# avr_programming_shield_built.net
KiCad netlist of a schematic drawn in EAGLE
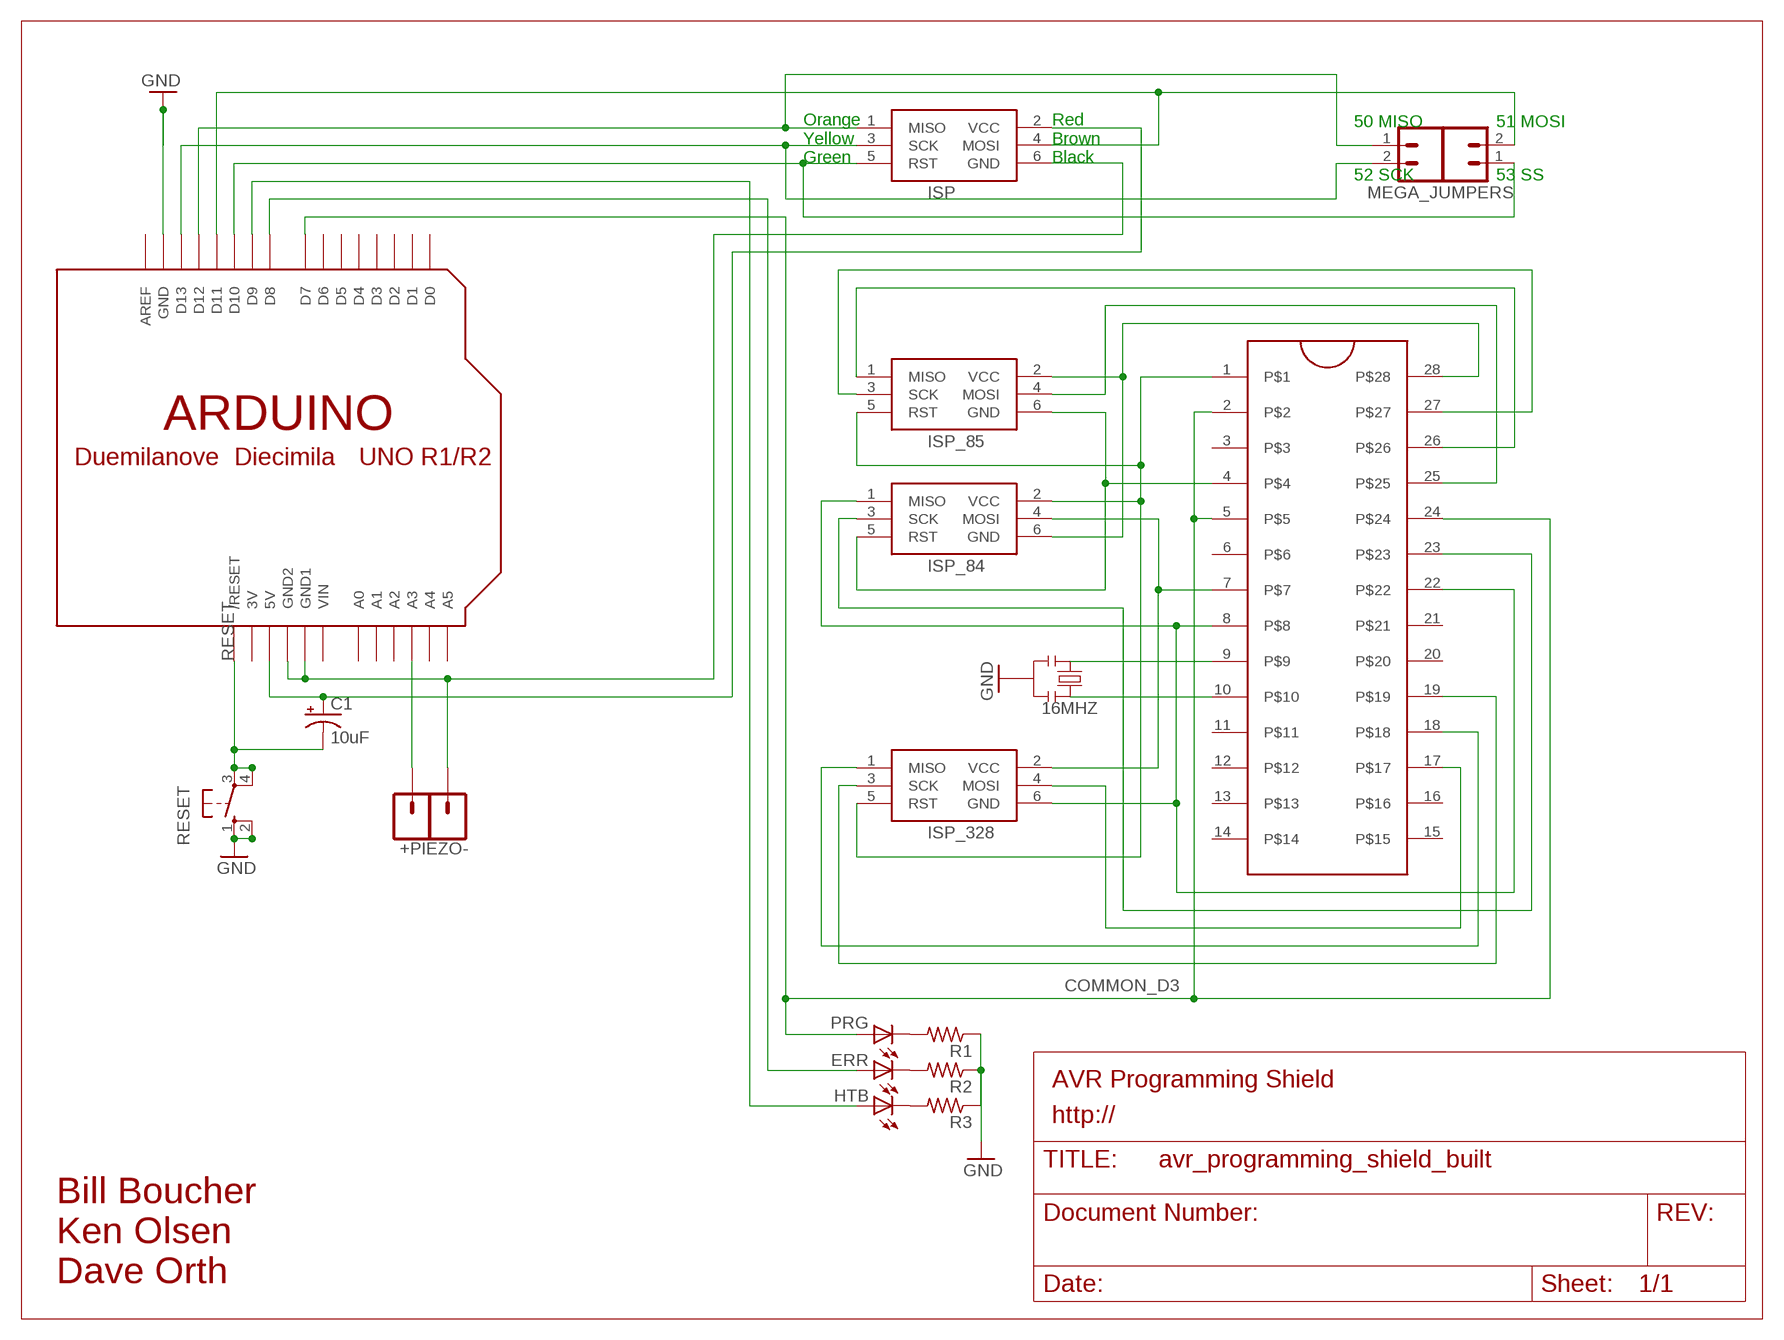
[diagram p0: schematic, sheet 1]

(export (version "E")
  (design (tool "Eeschema 10.0.6"))
  (components
    (comp (ref "+PIEZO-")
      (value "M01PTH")
      (footprint "eagle-import:1X01")
      (libsource (lib "eagle-import") (part "M01PTH"))
    )
    (comp (ref "16MHZ")
      (value "RESONATORPTH")
      (footprint "eagle-import:RESONATOR-PTH")
      (libsource (lib "eagle-import") (part "RESONATORPTH"))
    )
    (comp (ref "C1")
      (value "10uF")
      (footprint "eagle-import:CPOL-RADIAL-10UF-25V")
      (fields (field (name "MF") "ILLINOIS CAPACITOR,INC.") (field (name "MPN") "106TTA035M"))
      (libsource (lib "eagle-import") (part "CAP_POLPTH2"))
    )
    (comp (ref "ERR")
      (value "LED3MM")
      (footprint "eagle-import:LED3MM")
      (libsource (lib "eagle-import") (part "LED3MM"))
    )
    (comp (ref "HTB")
      (value "LED3MM")
      (footprint "eagle-import:LED3MM")
      (libsource (lib "eagle-import") (part "LED3MM"))
    )
    (comp (ref "ISP")
      (value "AVRISP-6")
      (footprint "eagle-import:AVRISP")
      (libsource (lib "eagle-import") (part "AVRISP-6"))
    )
    (comp (ref "ISP_84")
      (value "AVRISP-6")
      (footprint "eagle-import:AVRISP")
      (libsource (lib "eagle-import") (part "AVRISP-6"))
    )
    (comp (ref "ISP_85")
      (value "AVRISP-6")
      (footprint "eagle-import:AVRISP")
      (libsource (lib "eagle-import") (part "AVRISP-6"))
    )
    (comp (ref "ISP_328")
      (value "AVRISP-6")
      (footprint "eagle-import:AVRISP")
      (libsource (lib "eagle-import") (part "AVRISP-6"))
    )
    (comp (ref "JP2")
      (value "M02PTH")
      (footprint "eagle-import:1X02")
      (libsource (lib "eagle-import") (part "M02PTH"))
    )
    (comp (ref "JP4")
      (value "M01PTH")
      (footprint "eagle-import:1X01")
      (libsource (lib "eagle-import") (part "M01PTH"))
    )
    (comp (ref "MEGA_JUMPERS")
      (value "M02PTH")
      (footprint "eagle-import:1X02")
      (libsource (lib "eagle-import") (part "M02PTH"))
    )
    (comp (ref "PRG")
      (value "LED3MM")
      (footprint "eagle-import:LED3MM")
      (libsource (lib "eagle-import") (part "LED3MM"))
    )
    (comp (ref "R1")
      (value "R-US_0204/2V")
      (footprint "eagle-import:0204V")
      (libsource (lib "eagle-import") (part "R-US_0204/2V"))
    )
    (comp (ref "R2")
      (value "R-US_0204/2V")
      (footprint "eagle-import:0204V")
      (libsource (lib "eagle-import") (part "R-US_0204/2V"))
    )
    (comp (ref "R3")
      (value "R-US_0204/2V")
      (footprint "eagle-import:0204V")
      (libsource (lib "eagle-import") (part "R-US_0204/2V"))
    )
    (comp (ref "RESET")
      (value "10-XX")
      (footprint "eagle-import:B3F-10XX")
      (fields
        (field (name "MPN") "B3F-1000")
        (field (name "MPN_1") "B3F-1000")
        (field (name "OC_NEWARK") "36M3542")
      )
      (libsource (lib "eagle-import") (part "10-XX"))
    )
    (comp (ref "U$1")
      (value "ARDUINO-NOHOLE")
      (footprint "eagle-import:ARDUINO-NOHOLE")
      (libsource (lib "eagle-import") (part "ARDUINO-NOHOLE"))
    )
    (comp (ref "U$4")
      (value "ZIFSOCKET-28-3ZIFFSOCKET-28-3")
      (footprint "eagle-import:DIL28-3-ZIF_SOCKET")
      (libsource (lib "eagle-import") (part "ZIFSOCKET-28-3ZIFFSOCKET-28-3"))
    )
  )
  (nets
    (net (code "1") (name "/3V") (class "Default")
      (node (ref "U$1") (pin "3V") (pinfunction "3V_3V") (pintype "power_in"))
    )
    (net (code "2") (name "/COMMON_D3") (class "Default")
      (node (ref "PRG") (pin "A") (pinfunction "A_A") (pintype "passive"))
      (node (ref "U$1") (pin "D7") (pinfunction "D7_D7") (pintype "bidirectional"))
      (node (ref "U$4") (pin "2") (pinfunction "P$2_2") (pintype "bidirectional"))
      (node (ref "U$4") (pin "24") (pinfunction "P$24_24") (pintype "bidirectional"))
      (node (ref "U$4") (pin "5") (pinfunction "P$5_5") (pintype "bidirectional"))
    )
    (net (code "3") (name "/RESET") (class "Default")
      (node (ref "C1") (pin "2") (pinfunction "-_2") (pintype "passive"))
      (node (ref "RESET") (pin "3") (pinfunction "P_3") (pintype "passive"))
      (node (ref "RESET") (pin "4") (pinfunction "P1_4") (pintype "passive"))
      (node (ref "U$1") (pin "RESET") (pinfunction "/RESET_RESET") (pintype "bidirectional"))
    )
    (net (code "4") (name "/VIN") (class "Default")
      (node (ref "U$1") (pin "VIN") (pinfunction "VIN_VIN") (pintype "power_in"))
    )
    (net (code "5") (name "GND") (class "Default")
      (node (ref "+PIEZO-") (pin "1") (pinfunction "1_1") (pintype "passive"))
      (node (ref "16MHZ") (pin "2") (pinfunction "2_2") (pintype "passive"))
      (node (ref "ISP") (pin "6") (pinfunction "GND_6") (pintype "power_in"))
      (node (ref "R1") (pin "1") (pinfunction "1_1") (pintype "passive"))
      (node (ref "R2") (pin "1") (pinfunction "1_1") (pintype "passive"))
      (node (ref "R3") (pin "1") (pinfunction "1_1") (pintype "passive"))
      (node (ref "RESET") (pin "1") (pinfunction "S_1") (pintype "passive"))
      (node (ref "RESET") (pin "2") (pinfunction "S1_2") (pintype "passive"))
      (node (ref "U$1") (pin "GND") (pinfunction "GND_GND") (pintype "power_in"))
      (node (ref "U$1") (pin "GND1") (pinfunction "GND1_GND1") (pintype "power_in"))
      (node (ref "U$1") (pin "GND2") (pinfunction "GND2_GND2") (pintype "power_in"))
    )
    (net (code "6") (name "Net-(C1-+)") (class "Default")
      (node (ref "C1") (pin "1") (pinfunction "+_1") (pintype "passive"))
      (node (ref "ISP") (pin "2") (pinfunction "VCC_2") (pintype "power_in"))
      (node (ref "U$1") (pin "5V") (pinfunction "5V_5V") (pintype "power_in"))
    )
    (net (code "7") (name "Net-(ERR-C)") (class "Default")
      (node (ref "ERR") (pin "K") (pinfunction "C_K") (pintype "passive"))
      (node (ref "R2") (pin "2") (pinfunction "2_2") (pintype "passive"))
    )
    (net (code "8") (name "Net-(ERR-PadA)") (class "Default")
      (node (ref "ERR") (pin "A") (pinfunction "A_A") (pintype "passive"))
      (node (ref "U$1") (pin "D8") (pinfunction "D8_D8") (pintype "bidirectional"))
    )
    (net (code "9") (name "Net-(HTB-C)") (class "Default")
      (node (ref "HTB") (pin "K") (pinfunction "C_K") (pintype "passive"))
      (node (ref "R3") (pin "2") (pinfunction "2_2") (pintype "passive"))
    )
    (net (code "10") (name "Net-(HTB-PadA)") (class "Default")
      (node (ref "HTB") (pin "A") (pinfunction "A_A") (pintype "passive"))
      (node (ref "U$1") (pin "D9") (pinfunction "D9_D9") (pintype "bidirectional"))
    )
    (net (code "11") (name "Net-(ISP-MISO)") (class "Default")
      (node (ref "ISP") (pin "1") (pinfunction "MISO_1") (pintype "input"))
      (node (ref "MEGA_JUMPERS") (pin "1") (pinfunction "1_1") (pintype "passive"))
      (node (ref "U$1") (pin "D12") (pinfunction "D12_D12") (pintype "bidirectional"))
    )
    (net (code "12") (name "Net-(ISP-MOSI)") (class "Default")
      (node (ref "ISP") (pin "4") (pinfunction "MOSI_4") (pintype "output"))
      (node (ref "JP2") (pin "2") (pinfunction "2_2") (pintype "passive"))
      (node (ref "U$1") (pin "D11") (pinfunction "D11_D11") (pintype "bidirectional"))
    )
    (net (code "13") (name "Net-(ISP-RST)") (class "Default")
      (node (ref "ISP") (pin "5") (pinfunction "RST_5") (pintype "output"))
      (node (ref "JP2") (pin "1") (pinfunction "1_1") (pintype "passive"))
      (node (ref "U$1") (pin "D10") (pinfunction "D10_D10") (pintype "bidirectional"))
    )
    (net (code "14") (name "Net-(ISP-SCK)") (class "Default")
      (node (ref "ISP") (pin "3") (pinfunction "SCK_3") (pintype "output"))
      (node (ref "MEGA_JUMPERS") (pin "2") (pinfunction "2_2") (pintype "passive"))
      (node (ref "U$1") (pin "D13") (pinfunction "D13_D13") (pintype "bidirectional"))
    )
    (net (code "15") (name "Net-(ISP_84-GND)") (class "Default")
      (node (ref "ISP_84") (pin "6") (pinfunction "GND_6") (pintype "power_in"))
      (node (ref "ISP_85") (pin "2") (pinfunction "VCC_2") (pintype "power_in"))
      (node (ref "U$4") (pin "28") (pinfunction "P$28_28") (pintype "bidirectional"))
    )
    (net (code "16") (name "Net-(ISP_84-RST)") (class "Default")
      (node (ref "ISP_84") (pin "5") (pinfunction "RST_5") (pintype "output"))
      (node (ref "ISP_85") (pin "6") (pinfunction "GND_6") (pintype "power_in"))
      (node (ref "U$4") (pin "4") (pinfunction "P$4_4") (pintype "bidirectional"))
    )
    (net (code "17") (name "Net-(ISP_84-SCK)") (class "Default")
      (node (ref "ISP_84") (pin "3") (pinfunction "SCK_3") (pintype "output"))
      (node (ref "U$4") (pin "23") (pinfunction "P$23_23") (pintype "bidirectional"))
    )
    (net (code "18") (name "Net-(ISP_85-MISO)") (class "Default")
      (node (ref "ISP_85") (pin "1") (pinfunction "MISO_1") (pintype "input"))
      (node (ref "U$4") (pin "26") (pinfunction "P$26_26") (pintype "bidirectional"))
    )
    (net (code "19") (name "Net-(ISP_85-MOSI)") (class "Default")
      (node (ref "ISP_85") (pin "4") (pinfunction "MOSI_4") (pintype "output"))
      (node (ref "U$4") (pin "25") (pinfunction "P$25_25") (pintype "bidirectional"))
    )
    (net (code "20") (name "Net-(ISP_85-SCK)") (class "Default")
      (node (ref "ISP_85") (pin "3") (pinfunction "SCK_3") (pintype "output"))
      (node (ref "U$4") (pin "27") (pinfunction "P$27_27") (pintype "bidirectional"))
    )
    (net (code "21") (name "Net-(ISP_328-GND)") (class "Default")
      (node (ref "ISP_328") (pin "6") (pinfunction "GND_6") (pintype "power_in"))
      (node (ref "ISP_84") (pin "1") (pinfunction "MISO_1") (pintype "input"))
      (node (ref "U$4") (pin "22") (pinfunction "P$22_22") (pintype "bidirectional"))
      (node (ref "U$4") (pin "8") (pinfunction "P$8_8") (pintype "bidirectional"))
    )
    (net (code "22") (name "Net-(ISP_328-MISO)") (class "Default")
      (node (ref "ISP_328") (pin "1") (pinfunction "MISO_1") (pintype "input"))
      (node (ref "U$4") (pin "18") (pinfunction "P$18_18") (pintype "bidirectional"))
    )
    (net (code "23") (name "Net-(ISP_328-MOSI)") (class "Default")
      (node (ref "ISP_328") (pin "4") (pinfunction "MOSI_4") (pintype "output"))
      (node (ref "U$4") (pin "17") (pinfunction "P$17_17") (pintype "bidirectional"))
    )
    (net (code "24") (name "Net-(ISP_328-RST)") (class "Default")
      (node (ref "ISP_328") (pin "5") (pinfunction "RST_5") (pintype "output"))
      (node (ref "ISP_84") (pin "2") (pinfunction "VCC_2") (pintype "power_in"))
      (node (ref "ISP_85") (pin "5") (pinfunction "RST_5") (pintype "output"))
      (node (ref "U$4") (pin "1") (pinfunction "P$1_1") (pintype "bidirectional"))
    )
    (net (code "25") (name "Net-(ISP_328-SCK)") (class "Default")
      (node (ref "ISP_328") (pin "3") (pinfunction "SCK_3") (pintype "output"))
      (node (ref "U$4") (pin "19") (pinfunction "P$19_19") (pintype "bidirectional"))
    )
    (net (code "26") (name "Net-(ISP_328-VCC)") (class "Default")
      (node (ref "ISP_328") (pin "2") (pinfunction "VCC_2") (pintype "power_in"))
      (node (ref "ISP_84") (pin "4") (pinfunction "MOSI_4") (pintype "output"))
      (node (ref "U$4") (pin "7") (pinfunction "P$7_7") (pintype "bidirectional"))
    )
    (net (code "27") (name "Net-(JP4-Pad1)") (class "Default")
      (node (ref "JP4") (pin "1") (pinfunction "1_1") (pintype "passive"))
      (node (ref "U$1") (pin "A3") (pinfunction "A3_A3") (pintype "bidirectional"))
    )
    (net (code "28") (name "Net-(PRG-C)") (class "Default")
      (node (ref "PRG") (pin "K") (pinfunction "C_K") (pintype "passive"))
      (node (ref "R1") (pin "2") (pinfunction "2_2") (pintype "passive"))
    )
    (net (code "29") (name "Net-(U$4-P$9)") (class "Default")
      (node (ref "16MHZ") (pin "1") (pinfunction "1_1") (pintype "passive"))
      (node (ref "U$4") (pin "9") (pinfunction "P$9_9") (pintype "bidirectional"))
    )
    (net (code "30") (name "Net-(U$4-P$10)") (class "Default")
      (node (ref "16MHZ") (pin "3") (pinfunction "3_3") (pintype "passive"))
      (node (ref "U$4") (pin "10") (pinfunction "P$10_10") (pintype "bidirectional"))
    )
    (net (code "31") (name "unconnected-(U$1-PadA0)") (class "Default")
      (node (ref "U$1") (pin "A0") (pinfunction "A0_A0") (pintype "bidirectional"))
    )
    (net (code "32") (name "unconnected-(U$1-PadA1)") (class "Default")
      (node (ref "U$1") (pin "A1") (pinfunction "A1_A1") (pintype "bidirectional"))
    )
    (net (code "33") (name "unconnected-(U$1-PadA2)") (class "Default")
      (node (ref "U$1") (pin "A2") (pinfunction "A2_A2") (pintype "bidirectional"))
    )
    (net (code "34") (name "unconnected-(U$1-PadA4)") (class "Default")
      (node (ref "U$1") (pin "A4") (pinfunction "A4_A4") (pintype "bidirectional"))
    )
    (net (code "35") (name "unconnected-(U$1-PadA5)") (class "Default")
      (node (ref "U$1") (pin "A5") (pinfunction "A5_A5") (pintype "bidirectional"))
    )
    (net (code "36") (name "unconnected-(U$1-PadAREF)") (class "Default")
      (node (ref "U$1") (pin "AREF") (pinfunction "AREF_AREF") (pintype "bidirectional"))
    )
    (net (code "37") (name "unconnected-(U$1-PadD0)") (class "Default")
      (node (ref "U$1") (pin "D0") (pinfunction "D0_D0") (pintype "bidirectional"))
    )
    (net (code "38") (name "unconnected-(U$1-PadD1)") (class "Default")
      (node (ref "U$1") (pin "D1") (pinfunction "D1_D1") (pintype "bidirectional"))
    )
    (net (code "39") (name "unconnected-(U$1-PadD2)") (class "Default")
      (node (ref "U$1") (pin "D2") (pinfunction "D2_D2") (pintype "bidirectional"))
    )
    (net (code "40") (name "unconnected-(U$1-PadD3)") (class "Default")
      (node (ref "U$1") (pin "D3") (pinfunction "D3_D3") (pintype "bidirectional"))
    )
    (net (code "41") (name "unconnected-(U$1-PadD4)") (class "Default")
      (node (ref "U$1") (pin "D4") (pinfunction "D4_D4") (pintype "bidirectional"))
    )
    (net (code "42") (name "unconnected-(U$1-PadD5)") (class "Default")
      (node (ref "U$1") (pin "D5") (pinfunction "D5_D5") (pintype "bidirectional"))
    )
    (net (code "43") (name "unconnected-(U$1-PadD6)") (class "Default")
      (node (ref "U$1") (pin "D6") (pinfunction "D6_D6") (pintype "bidirectional"))
    )
    (net (code "44") (name "unconnected-(U$4-P$3-Pad3)") (class "Default")
      (node (ref "U$4") (pin "3") (pinfunction "P$3_3") (pintype "bidirectional"))
    )
    (net (code "45") (name "unconnected-(U$4-P$6-Pad6)") (class "Default")
      (node (ref "U$4") (pin "6") (pinfunction "P$6_6") (pintype "bidirectional"))
    )
    (net (code "46") (name "unconnected-(U$4-P$11-Pad11)") (class "Default")
      (node (ref "U$4") (pin "11") (pinfunction "P$11_11") (pintype "bidirectional"))
    )
    (net (code "47") (name "unconnected-(U$4-P$12-Pad12)") (class "Default")
      (node (ref "U$4") (pin "12") (pinfunction "P$12_12") (pintype "bidirectional"))
    )
    (net (code "48") (name "unconnected-(U$4-P$13-Pad13)") (class "Default")
      (node (ref "U$4") (pin "13") (pinfunction "P$13_13") (pintype "bidirectional"))
    )
    (net (code "49") (name "unconnected-(U$4-P$14-Pad14)") (class "Default")
      (node (ref "U$4") (pin "14") (pinfunction "P$14_14") (pintype "bidirectional"))
    )
    (net (code "50") (name "unconnected-(U$4-P$15-Pad15)") (class "Default")
      (node (ref "U$4") (pin "15") (pinfunction "P$15_15") (pintype "bidirectional"))
    )
    (net (code "51") (name "unconnected-(U$4-P$16-Pad16)") (class "Default")
      (node (ref "U$4") (pin "16") (pinfunction "P$16_16") (pintype "bidirectional"))
    )
    (net (code "52") (name "unconnected-(U$4-P$20-Pad20)") (class "Default")
      (node (ref "U$4") (pin "20") (pinfunction "P$20_20") (pintype "bidirectional"))
    )
    (net (code "53") (name "unconnected-(U$4-P$21-Pad21)") (class "Default")
      (node (ref "U$4") (pin "21") (pinfunction "P$21_21") (pintype "bidirectional"))
    )
  )
)
